# DeckunitV1.net
KiCad netlist of a schematic drawn in EAGLE
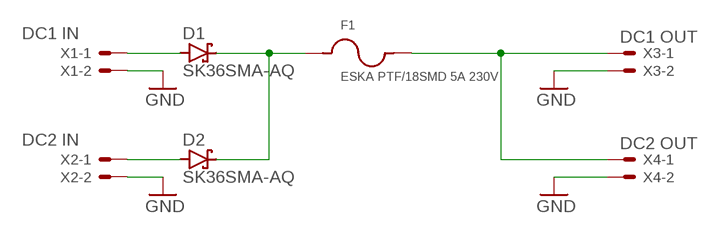
[diagram p0: schematic, sheet 1]

(export (version "E")
  (design (tool "Eeschema 10.0.6"))
  (components
    (comp (ref "D1")
      (value "SK36SMA-AQ")
      (footprint "eagle-import:SMA")
      (fields
        (field (name "DIGIKEY_PART_NUMBER") "SS12FSCT-ND")
        (field (name "MANUFACTURER") "ON Semiconductor")
        (field (name "MPN") "SS12")
        (field (name "CREATED_BY") "PCBLayout.com")
      )
      (libsource (lib "eagle-import") (part "SS12"))
    )
    (comp (ref "D2")
      (value "SK36SMA-AQ")
      (footprint "eagle-import:SMA")
      (fields
        (field (name "DIGIKEY_PART_NUMBER") "SS12FSCT-ND")
        (field (name "MANUFACTURER") "ON Semiconductor")
        (field (name "MPN") "SS12")
        (field (name "CREATED_BY") "PCBLayout.com")
      )
      (libsource (lib "eagle-import") (part "SS12"))
    )
    (comp (ref "F1")
      (value "ESKA PTF/18SMD 5A 230V")
      (footprint "eagle-import:65800001109")
      (fields
        (field (name "DIGIKEY_PARTNO") "WK6249TR-ND")
        (field (name "MANUFACTURER") "Littelfuse Inc.")
        (field (name "MPN") "65800001109")
        (field (name "CREATED_BY") "PCBLayout.com")
      )
      (libsource (lib "eagle-import") (part "65800001109"))
    )
    (comp (ref "X1")
      (value "DC1 IN")
      (footprint "eagle-import:2PIN")
      (libsource (lib "eagle-import") (part "22-23-20212PIN"))
    )
    (comp (ref "X2")
      (value "DC2 IN")
      (footprint "eagle-import:2PIN")
      (libsource (lib "eagle-import") (part "22-23-20212PIN"))
    )
    (comp (ref "X3")
      (value "DC1 OUT")
      (footprint "eagle-import:2PIN")
      (libsource (lib "eagle-import") (part "22-23-20212PIN"))
    )
    (comp (ref "X4")
      (value "DC2 OUT")
      (footprint "eagle-import:2PIN")
      (libsource (lib "eagle-import") (part "22-23-20212PIN"))
    )
  )
  (nets
    (net (code "1") (name "GND") (class "Default")
      (node (ref "X1") (pin "2") (pinfunction "S_2") (pintype "passive"))
      (node (ref "X2") (pin "2") (pinfunction "S_2") (pintype "passive"))
      (node (ref "X3") (pin "2") (pinfunction "S_2") (pintype "passive"))
      (node (ref "X4") (pin "2") (pinfunction "S_2") (pintype "passive"))
    )
    (net (code "2") (name "Net-(D1-PadC)") (class "Default")
      (node (ref "D1") (pin "C") (pinfunction "C_C") (pintype "passive"))
      (node (ref "D2") (pin "C") (pinfunction "C_C") (pintype "passive"))
      (node (ref "F1") (pin "1") (pinfunction "1_1") (pintype "passive"))
    )
    (net (code "3") (name "Net-(X1A-S)") (class "Default")
      (node (ref "D1") (pin "A") (pinfunction "A_A") (pintype "passive"))
      (node (ref "X1") (pin "1") (pinfunction "S_1") (pintype "passive"))
    )
    (net (code "4") (name "Net-(X2A-S)") (class "Default")
      (node (ref "D2") (pin "A") (pinfunction "A_A") (pintype "passive"))
      (node (ref "X2") (pin "1") (pinfunction "S_1") (pintype "passive"))
    )
    (net (code "5") (name "Net-(X3A-S)") (class "Default")
      (node (ref "F1") (pin "2") (pinfunction "2_2") (pintype "passive"))
      (node (ref "X3") (pin "1") (pinfunction "S_1") (pintype "passive"))
      (node (ref "X4") (pin "1") (pinfunction "S_1") (pintype "passive"))
    )
  )
)
